# Enclosure_100x68_BHWL.net
KiCad netlist of a schematic drawn in EAGLE
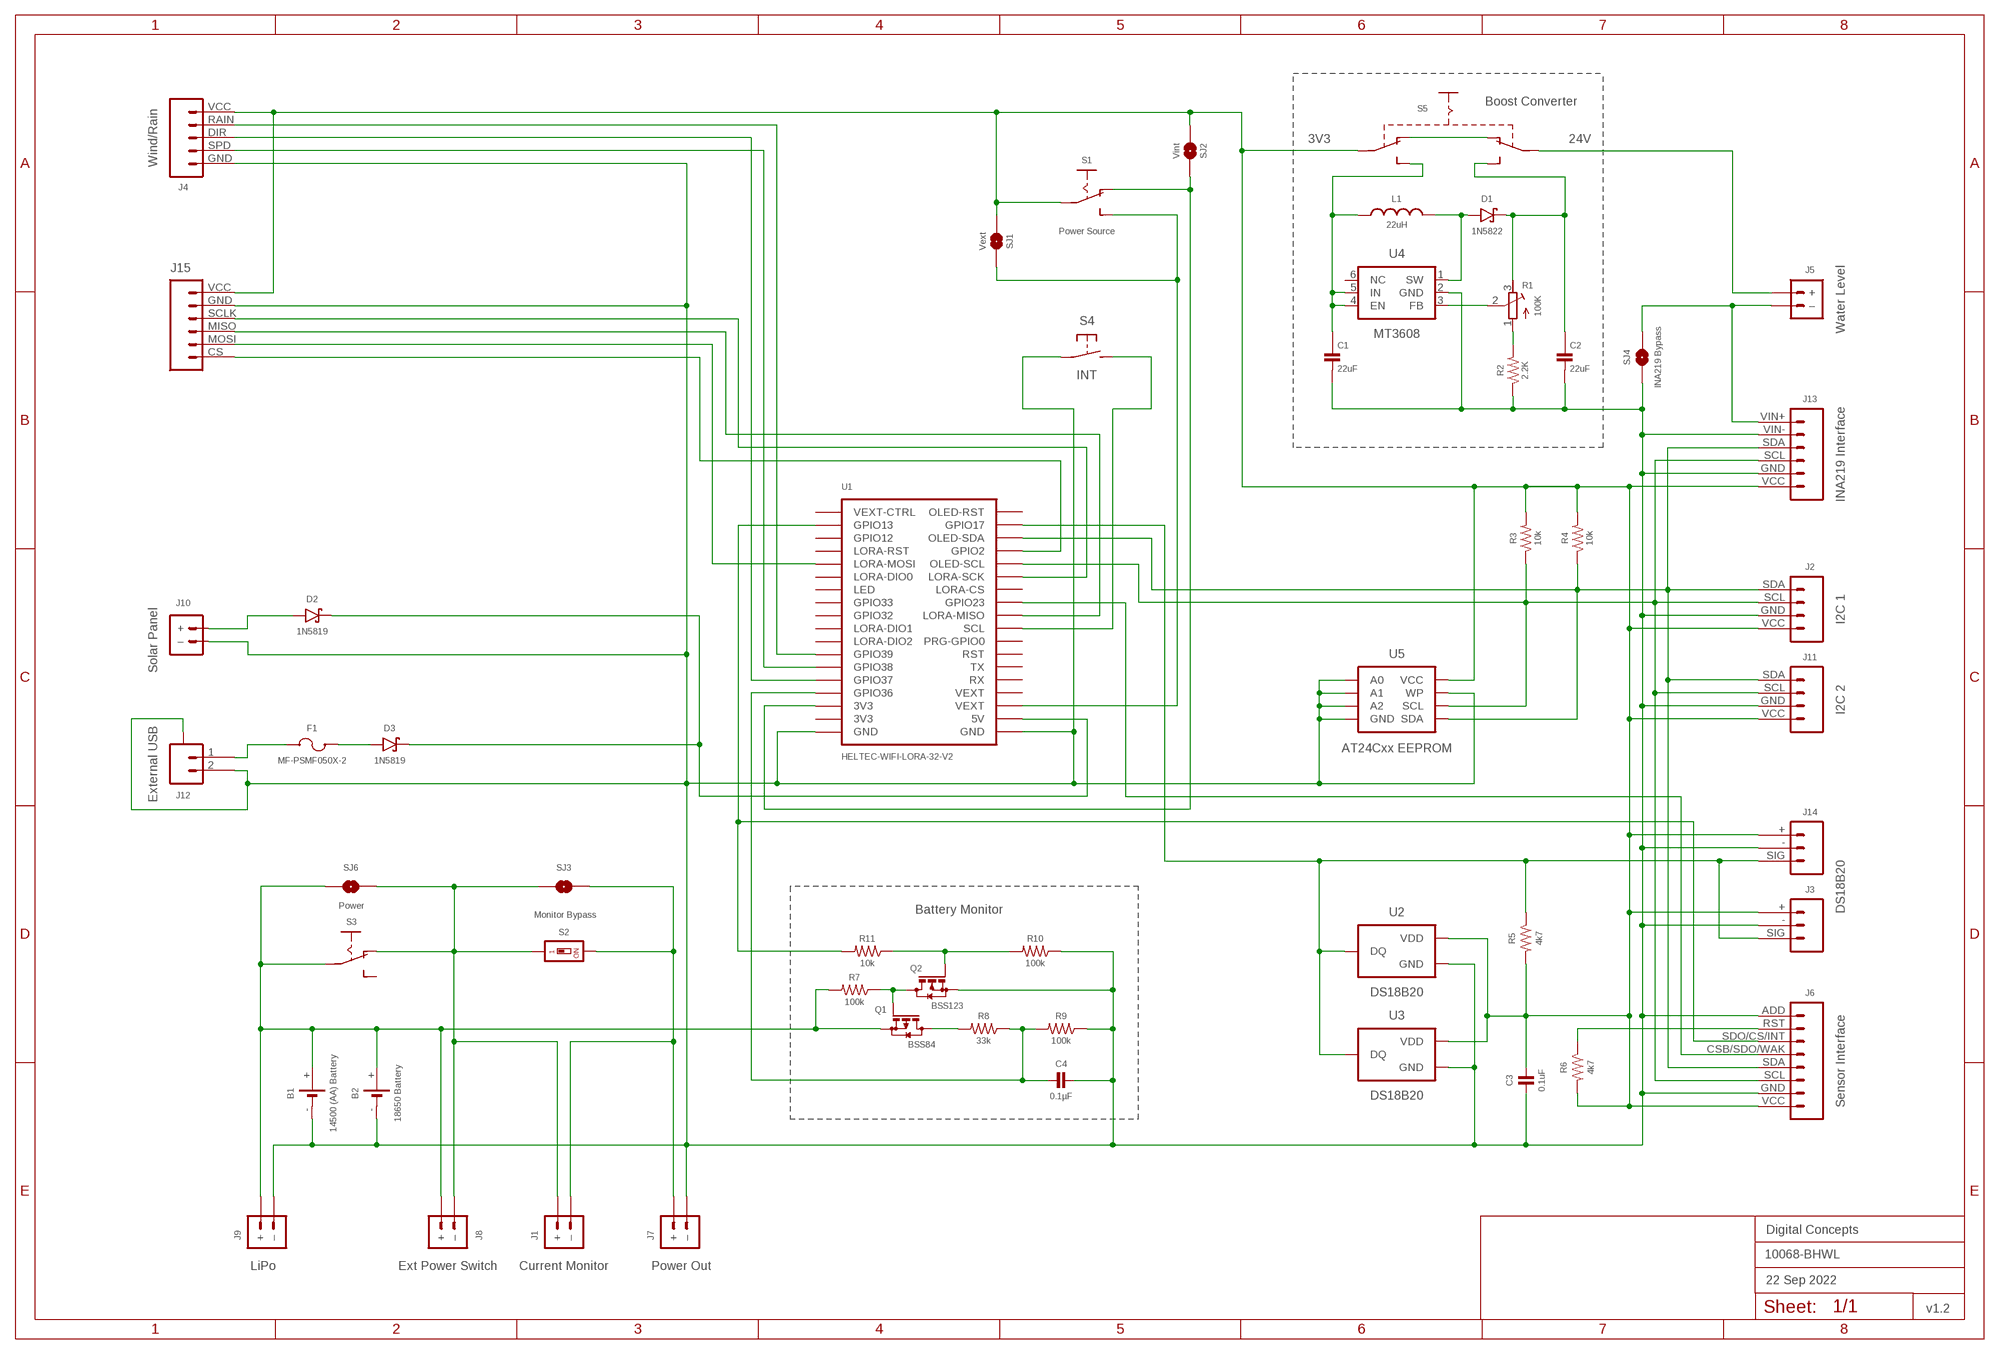
[diagram p0: schematic, sheet 1]

(export (version "E")
  (design (tool "Eeschema 10.0.6"))
  (components
    (comp (ref "B1")
      (value "14500 (AA) Battery")
      (footprint "eagle-import:BATTERY-14500")
      (libsource (lib "eagle-import") (part "BATTERY-HOLDER-14500(AA)"))
    )
    (comp (ref "B2")
      (value "18650 Battery")
      (footprint "eagle-import:BATTERY-18650")
      (libsource (lib "eagle-import") (part "BATTERY-HOLDER-18650"))
    )
    (comp (ref "C1")
      (value "22uF")
      (footprint "eagle-import:C1206")
      (libsource (lib "eagle-import") (part "CAPACITOR-1206"))
    )
    (comp (ref "C2")
      (value "22uF")
      (footprint "eagle-import:C1206")
      (libsource (lib "eagle-import") (part "CAPACITOR-1206"))
    )
    (comp (ref "C3")
      (value "0.1uF")
      (footprint "eagle-import:C0805")
      (libsource (lib "eagle-import") (part "CAPACITOR-0805"))
    )
    (comp (ref "C4")
      (value "0.1µF")
      (footprint "eagle-import:C0805")
      (libsource (lib "eagle-import") (part "CAPACITOR-0805"))
    )
    (comp (ref "D1")
      (value "1N5822")
      (footprint "eagle-import:DIODE_SMB")
      (libsource (lib "eagle-import") (part "DIODE-SCHOTTKY-1N5822"))
    )
    (comp (ref "D2")
      (value "1N5819")
      (footprint "eagle-import:SOD-123")
      (libsource (lib "eagle-import") (part "1N5819-SOD-123"))
    )
    (comp (ref "D3")
      (value "1N5819")
      (footprint "eagle-import:SOD-123")
      (libsource (lib "eagle-import") (part "1N5819-SOD-123"))
    )
    (comp (ref "F1")
      (value "MF-PSMF050X-2")
      (footprint "eagle-import:F0805")
      (libsource (lib "eagle-import") (part "MF-PSMF050X-2"))
    )
    (comp (ref "J1")
      (value "Current Monitor")
      (footprint "eagle-import:JST-PH2.0-2-HORIZONTAL")
      (libsource (lib "eagle-import") (part "JST-PH2.0-2-HORIZONTALJST-PTH-2"))
    )
    (comp (ref "J2")
      (value "I2C 1")
      (footprint "eagle-import:JST-PH2.0-4-VERTICAL-I2C")
      (libsource (lib "eagle-import") (part "JST-PH2.0-4-VERTICAL-I2C"))
    )
    (comp (ref "J3")
      (value "DS18B20")
      (footprint "eagle-import:JST-PH2.0-3-VERTICAL-SIG")
      (libsource (lib "eagle-import") (part "JST-PH2.0-3-VERTICAL-DS18B20"))
    )
    (comp (ref "J4")
      (value "Wind/Rain")
      (footprint "eagle-import:JST-PH2.0-5-DUAL-WEATHER")
      (libsource (lib "eagle-import") (part "JST-PH2.0-5-DUAL-WEATHER"))
    )
    (comp (ref "J5")
      (value "Water Level")
      (footprint "eagle-import:JST-PH2.0-2-DUAL-POWER")
      (libsource (lib "eagle-import") (part "JST-PH2.0-2-DUAL-POWERJST-PTH-2"))
    )
    (comp (ref "J6")
      (value "Sensor Interface")
      (footprint "eagle-import:CONN_08-SENSOR")
      (libsource (lib "eagle-import") (part "HEADER-1X8-SENSOR"))
    )
    (comp (ref "J7")
      (value "Power Out")
      (footprint "eagle-import:JST-GH1.25-2-HORIZONTAL")
      (libsource (lib "eagle-import") (part "JST-GH1.25-2-HORIZONTAL-POWER"))
    )
    (comp (ref "J8")
      (value "Ext Power Switch")
      (footprint "eagle-import:JST-PH2.0-2-DUAL-POWER")
      (libsource (lib "eagle-import") (part "JST-PH2.0-2-DUAL-POWERJST-PTH-2"))
    )
    (comp (ref "J9")
      (value "LiPo")
      (footprint "eagle-import:JST-PH2.0-2-HORIZONTAL-POWER")
      (libsource (lib "eagle-import") (part "JST-PH2.0-2-HORIZONTAL-POWERJST-PTH-2"))
    )
    (comp (ref "J10")
      (value "Solar Panel")
      (footprint "eagle-import:JST-PH2.0-2-VERTICAL=POWER")
      (libsource (lib "eagle-import") (part "JST-PH2.0-2-VERTICAL"))
    )
    (comp (ref "J11")
      (value "I2C 2")
      (footprint "eagle-import:JST-PH2.0-4-HORIZONTAL")
      (libsource (lib "eagle-import") (part "JST-PH2.0-I2C-MALE-HORIZONTAL"))
    )
    (comp (ref "J12")
      (value "External USB")
      (footprint "eagle-import:JST-SH1.0-2-HORIZONTAL")
      (libsource (lib "eagle-import") (part "JST-SH1.0-2-SMD-HORIZONTAL"))
    )
    (comp (ref "J13")
      (value "INA219 Interface")
      (footprint "eagle-import:CONN_06-INA219")
      (libsource (lib "eagle-import") (part "INA219-I2C-MODULE"))
    )
    (comp (ref "J14")
      (value "JST-PH2.0-3-HORIZONTAL-DS18B20")
      (footprint "eagle-import:JST-PH2.0-DS18B20-HORIZONTAL")
      (libsource (lib "eagle-import") (part "JST-PH2.0-3-HORIZONTAL-DS18B20"))
    )
    (comp (ref "J15")
      (value "JST-PH2.0-6-HORIZONTAL-SPI")
      (footprint "eagle-import:JST-PH2.0-6-HORIZONTAL-SPI")
      (libsource (lib "eagle-import") (part "JST-PH2.0-6-HORIZONTAL-SPI"))
    )
    (comp (ref "L1")
      (value "22uH")
      (footprint "eagle-import:CDRH104R+6D28")
      (libsource (lib "eagle-import") (part "INDUCTOR-CDRH104R/6D28L5038P"))
    )
    (comp (ref "Q1")
      (value "BSS84")
      (footprint "eagle-import:SOT23-3")
      (libsource (lib "eagle-import") (part "BSS84"))
    )
    (comp (ref "Q2")
      (value "BSS123")
      (footprint "eagle-import:SOT23-3")
      (libsource (lib "eagle-import") (part "MOSFET-BSS123"))
    )
    (comp (ref "R1")
      (value "100K")
      (footprint "eagle-import:RTRIM64P")
      (libsource (lib "eagle-import") (part "RESISTOR-TRIMM-BAOTER-HORIZONTAL"))
    )
    (comp (ref "R2")
      (value "2.2K")
      (footprint "eagle-import:R0805")
      (libsource (lib "eagle-import") (part "RESISTORR0805"))
    )
    (comp (ref "R3")
      (value "10k")
      (footprint "eagle-import:R0805")
      (libsource (lib "eagle-import") (part "RESISTORR0805"))
    )
    (comp (ref "R4")
      (value "10k")
      (footprint "eagle-import:R0805")
      (libsource (lib "eagle-import") (part "RESISTORR0805"))
    )
    (comp (ref "R5")
      (value "4k7")
      (footprint "eagle-import:R0805")
      (libsource (lib "eagle-import") (part "RESISTORR0805"))
    )
    (comp (ref "R6")
      (value "4k7")
      (footprint "eagle-import:R0805")
      (libsource (lib "eagle-import") (part "RESISTORR0805"))
    )
    (comp (ref "R7")
      (value "100k")
      (footprint "eagle-import:R0805")
      (libsource (lib "eagle-import") (part "RESISTORR0805"))
    )
    (comp (ref "R8")
      (value "33k")
      (footprint "eagle-import:R0805")
      (libsource (lib "eagle-import") (part "RESISTORR0805"))
    )
    (comp (ref "R9")
      (value "100k")
      (footprint "eagle-import:R0805")
      (libsource (lib "eagle-import") (part "RESISTORR0805"))
    )
    (comp (ref "R10")
      (value "100k")
      (footprint "eagle-import:R0805")
      (libsource (lib "eagle-import") (part "RESISTORR0805"))
    )
    (comp (ref "R11")
      (value "10k")
      (footprint "eagle-import:R0805")
      (libsource (lib "eagle-import") (part "RESISTORR0805"))
    )
    (comp (ref "S1")
      (value "Power Source")
      (footprint "eagle-import:SWITCH-SPDT-SMT")
      (libsource (lib "eagle-import") (part "SWITCH-SLIDE-SPDT-SMT"))
    )
    (comp (ref "S2")
      (value "Monitor Bypass")
      (footprint "eagle-import:SMD-001")
      (libsource (lib "eagle-import") (part "SWITCH-DIP-SWS001"))
    )
    (comp (ref "S3")
      (value "Power")
      (footprint "eagle-import:SWITCH-SPDT-PTH")
      (libsource (lib "eagle-import") (part "SWITCH-SLIDE-SPDT-PTH"))
    )
    (comp (ref "S4")
      (value "INT")
      (footprint "eagle-import:SWITCH-2-PAD")
      (libsource (lib "eagle-import") (part "SWITCH-MOMENTARY-2-PIN"))
    )
    (comp (ref "S5")
      (value "SWITCH-SLIDE-DPDT-PTH-S")
      (footprint "eagle-import:SWITCH-DPDT-PTH")
      (libsource (lib "eagle-import") (part "SWITCH-SLIDE-DPDT-PTH-S"))
    )
    (comp (ref "SJ1")
      (value "Vext")
      (footprint "eagle-import:SJ")
      (libsource (lib "eagle-import") (part "SJ"))
    )
    (comp (ref "SJ2")
      (value "Vint")
      (footprint "eagle-import:SJ-VIA-2")
      (libsource (lib "eagle-import") (part "SJ-V-2"))
    )
    (comp (ref "SJ3")
      (value "Monitor")
      (footprint "eagle-import:SJ")
      (libsource (lib "eagle-import") (part "SJ"))
    )
    (comp (ref "SJ4")
      (value "INA219 Bypass")
      (footprint "eagle-import:SJ")
      (libsource (lib "eagle-import") (part "SJ"))
    )
    (comp (ref "SJ6")
      (value "Power")
      (footprint "eagle-import:SJ")
      (libsource (lib "eagle-import") (part "SJ"))
    )
    (comp (ref "U1")
      (value "HELTEC-WIFI-LORA-32-V2")
      (footprint "eagle-import:HELTEC-WIFI-LORA-32-V2")
      (libsource (lib "eagle-import") (part "HELTEC-WIFI-LORA-32-V2"))
    )
    (comp (ref "U2")
      (value "DS18B20")
      (footprint "eagle-import:TO-92")
      (fields (field (name "MF") "Maxim Integrated"))
      (libsource (lib "eagle-import") (part "THERMOMETER-DS18B20"))
    )
    (comp (ref "U3")
      (value "DS18B20")
      (footprint "eagle-import:TO-92")
      (fields (field (name "MF") "Maxim Integrated"))
      (libsource (lib "eagle-import") (part "THERMOMETER-DS18B20"))
    )
    (comp (ref "U4")
      (value "MT3608")
      (footprint "eagle-import:SOT-23-6")
      (libsource (lib "eagle-import") (part "MT3608"))
    )
    (comp (ref "U5")
      (value "AT24Cxx EEPROM")
      (footprint "eagle-import:SOP-8")
      (libsource (lib "eagle-import") (part "AT24CXX-EEPROM"))
    )
  )
  (nets
    (net (code "1") (name "Net-(C4-Pad1)") (class "Default")
      (node (ref "C4") (pin "1") (pinfunction "1_1") (pintype "passive"))
      (node (ref "R8") (pin "1") (pinfunction "1_1") (pintype "passive"))
      (node (ref "R9") (pin "2") (pinfunction "2_2") (pintype "passive"))
      (node (ref "U1") (pin "GPIO36") (pinfunction "GPIO36_GPIO36") (pintype "bidirectional"))
    )
    (net (code "2") (name "Net-(D2-PadA)") (class "Default")
      (node (ref "D2") (pin "A") (pinfunction "A_A") (pintype "passive"))
      (node (ref "J10") (pin "+") (pinfunction "+_+") (pintype "power_in"))
    )
    (net (code "3") (name "Net-(D2-PadC)") (class "Default")
      (node (ref "D2") (pin "C") (pinfunction "C_C") (pintype "passive"))
      (node (ref "D3") (pin "C") (pinfunction "C_C") (pintype "passive"))
      (node (ref "U1") (pin "5V") (pinfunction "5V_5V") (pintype "bidirectional"))
    )
    (net (code "4") (name "Net-(D3-PadA)") (class "Default")
      (node (ref "D3") (pin "A") (pinfunction "A_A") (pintype "passive"))
      (node (ref "F1") (pin "1") (pinfunction "1_1") (pintype "passive"))
    )
    (net (code "5") (name "Net-(F1-Pad2)") (class "Default")
      (node (ref "F1") (pin "2") (pinfunction "2_2") (pintype "passive"))
      (node (ref "J12") (pin "1") (pinfunction "1_1") (pintype "passive"))
    )
    (net (code "6") (name "Net-(J1-+)") (class "Default")
      (node (ref "J1") (pin "1") (pinfunction "+_1") (pintype "power_in"))
      (node (ref "J8") (pin "-") (pinfunction "–_-") (pintype "power_in"))
      (node (ref "S2") (pin "1") (pinfunction "1_1") (pintype "passive"))
      (node (ref "S3") (pin "1") (pinfunction "O_1") (pintype "passive"))
      (node (ref "SJ3") (pin "2") (pinfunction "2_2") (pintype "passive"))
      (node (ref "SJ6") (pin "1") (pinfunction "1_1") (pintype "passive"))
    )
    (net (code "7") (name "Net-(J1-–)") (class "Default")
      (node (ref "J1") (pin "2") (pinfunction "–_2") (pintype "power_in"))
      (node (ref "J7") (pin "+") (pinfunction "+_+") (pintype "power_in"))
      (node (ref "S2") (pin "2") (pinfunction "2_2") (pintype "passive"))
      (node (ref "SJ3") (pin "1") (pinfunction "1_1") (pintype "passive"))
    )
    (net (code "8") (name "Net-(J4-2)") (class "Default")
      (node (ref "J4") (pin "RAIN") (pinfunction "2_RAIN") (pintype "passive"))
      (node (ref "U1") (pin "GPIO39") (pinfunction "GPIO39_GPIO39") (pintype "bidirectional"))
    )
    (net (code "9") (name "Net-(J4-3)") (class "Default")
      (node (ref "J4") (pin "DIR") (pinfunction "3_DIR") (pintype "passive"))
      (node (ref "U1") (pin "GPIO37") (pinfunction "GPIO37_GPIO37") (pintype "bidirectional"))
    )
    (net (code "10") (name "Net-(J4-4)") (class "Default")
      (node (ref "J4") (pin "SPD") (pinfunction "4_SPD") (pintype "passive"))
      (node (ref "U1") (pin "GPIO38") (pinfunction "GPIO38_GPIO38") (pintype "bidirectional"))
    )
    (net (code "11") (name "Net-(J6-5)") (class "Default")
      (node (ref "J6") (pin "CSB/SDO/WAK") (pinfunction "5_CSB/SDO/WAK") (pintype "passive"))
      (node (ref "U1") (pin "GPIO23") (pinfunction "GPIO23_GPIO23") (pintype "bidirectional"))
    )
    (net (code "12") (name "Net-(J6-6)") (class "Default")
      (node (ref "J6") (pin "SDO/CS/INT") (pinfunction "6_SDO/CS/INT") (pintype "passive"))
      (node (ref "R11") (pin "2") (pinfunction "2_2") (pintype "passive"))
      (node (ref "U1") (pin "GPIO13") (pinfunction "GPIO13_GPIO13") (pintype "bidirectional"))
    )
    (net (code "13") (name "Net-(J6-7)") (class "Default")
      (node (ref "J6") (pin "RST") (pinfunction "7_RST") (pintype "passive"))
      (node (ref "R6") (pin "1") (pinfunction "1_1") (pintype "passive"))
    )
    (net (code "14") (name "Net-(J10-–)") (class "Default")
      (node (ref "B1") (pin "-") (pinfunction "-_-") (pintype "power_in"))
      (node (ref "B2") (pin "-") (pinfunction "-_-") (pintype "power_in"))
      (node (ref "C1") (pin "2") (pinfunction "2_2") (pintype "passive"))
      (node (ref "C2") (pin "2") (pinfunction "2_2") (pintype "passive"))
      (node (ref "C3") (pin "2") (pinfunction "2_2") (pintype "passive"))
      (node (ref "C4") (pin "2") (pinfunction "2_2") (pintype "passive"))
      (node (ref "J10") (pin "-") (pinfunction "–_-") (pintype "power_in"))
      (node (ref "J11") (pin "GND") (pinfunction "2_GND") (pintype "passive"))
      (node (ref "J12") (pin "2") (pinfunction "2_2") (pintype "passive"))
      (node (ref "J12") (pin "A@1") (pinfunction "A_A@1") (pintype "power_in"))
      (node (ref "J12") (pin "A@2") (pinfunction "A_A@2") (pintype "power_in"))
      (node (ref "J13") (pin "GND") (pinfunction "2_GND") (pintype "passive"))
      (node (ref "J13") (pin "VIN-") (pinfunction "5_VIN-") (pintype "passive"))
      (node (ref "J14") (pin "-") (pinfunction "2_-") (pintype "passive"))
      (node (ref "J15") (pin "GND") (pinfunction "5_GND") (pintype "passive"))
      (node (ref "J2") (pin "GND") (pinfunction "3_GND") (pintype "passive"))
      (node (ref "J3") (pin "-") (pinfunction "2_-") (pintype "passive"))
      (node (ref "J4") (pin "GND") (pinfunction "5_GND") (pintype "passive"))
      (node (ref "J6") (pin "ADD") (pinfunction "8_ADD") (pintype "passive"))
      (node (ref "J6") (pin "GND") (pinfunction "2_GND") (pintype "passive"))
      (node (ref "J7") (pin "-") (pinfunction "–_-") (pintype "power_in"))
      (node (ref "J9") (pin "-") (pinfunction "–_-") (pintype "power_in"))
      (node (ref "Q2") (pin "2") (pinfunction "S_2") (pintype "passive"))
      (node (ref "R10") (pin "1") (pinfunction "1_1") (pintype "passive"))
      (node (ref "R2") (pin "1") (pinfunction "1_1") (pintype "passive"))
      (node (ref "R9") (pin "1") (pinfunction "1_1") (pintype "passive"))
      (node (ref "S4") (pin "P$1") (pinfunction "P_P$1") (pintype "passive"))
      (node (ref "SJ4") (pin "1") (pinfunction "1_1") (pintype "passive"))
      (node (ref "U1") (pin "GND@1") (pinfunction "GND_GND@1") (pintype "bidirectional"))
      (node (ref "U1") (pin "GND@36") (pinfunction "GND_GND@36") (pintype "bidirectional"))
      (node (ref "U2") (pin "1") (pinfunction "GND_1") (pintype "power_in"))
      (node (ref "U3") (pin "1") (pinfunction "GND_1") (pintype "power_in"))
      (node (ref "U4") (pin "2") (pinfunction "GND_2") (pintype "power_in"))
      (node (ref "U5") (pin "P$1") (pinfunction "A0_P$1") (pintype "bidirectional"))
      (node (ref "U5") (pin "P$2") (pinfunction "A1_P$2") (pintype "bidirectional"))
      (node (ref "U5") (pin "P$3") (pinfunction "A2_P$3") (pintype "bidirectional"))
      (node (ref "U5") (pin "P$4") (pinfunction "GND_P$4") (pintype "bidirectional"))
      (node (ref "U5") (pin "P$7") (pinfunction "WP_P$7") (pintype "bidirectional"))
    )
    (net (code "15") (name "Net-(J11-1)") (class "Default")
      (node (ref "C3") (pin "1") (pinfunction "1_1") (pintype "passive"))
      (node (ref "J11") (pin "VCC") (pinfunction "1_VCC") (pintype "passive"))
      (node (ref "J13") (pin "VCC") (pinfunction "1_VCC") (pintype "passive"))
      (node (ref "J14") (pin "+") (pinfunction "3_+") (pintype "passive"))
      (node (ref "J15") (pin "VCC") (pinfunction "6_VCC") (pintype "passive"))
      (node (ref "J2") (pin "VCC") (pinfunction "4_VCC") (pintype "passive"))
      (node (ref "J3") (pin "+") (pinfunction "3_+") (pintype "passive"))
      (node (ref "J4") (pin "VCC") (pinfunction "1_VCC") (pintype "passive"))
      (node (ref "J6") (pin "VCC") (pinfunction "1_VCC") (pintype "passive"))
      (node (ref "R3") (pin "2") (pinfunction "2_2") (pintype "passive"))
      (node (ref "R4") (pin "2") (pinfunction "2_2") (pintype "passive"))
      (node (ref "R5") (pin "2") (pinfunction "2_2") (pintype "passive"))
      (node (ref "R6") (pin "2") (pinfunction "2_2") (pintype "passive"))
      (node (ref "S1") (pin "2") (pinfunction "P_2") (pintype "passive"))
      (node (ref "S5") (pin "P$5") (pinfunction "P2_P$5") (pintype "passive"))
      (node (ref "SJ1") (pin "2") (pinfunction "2_2") (pintype "passive"))
      (node (ref "SJ2") (pin "2") (pinfunction "2_2") (pintype "passive"))
      (node (ref "SJ2") (pin "2@V") (pinfunction "2_2@V") (pintype "passive"))
      (node (ref "U2") (pin "3") (pinfunction "VDD_3") (pintype "power_in"))
      (node (ref "U3") (pin "3") (pinfunction "VDD_3") (pintype "power_in"))
      (node (ref "U5") (pin "P$8") (pinfunction "VCC_P$8") (pintype "bidirectional"))
    )
    (net (code "16") (name "Net-(J11-3)") (class "Default")
      (node (ref "J11") (pin "SCL") (pinfunction "3_SCL") (pintype "passive"))
      (node (ref "J13") (pin "SCL") (pinfunction "3_SCL") (pintype "passive"))
      (node (ref "J2") (pin "SCL") (pinfunction "2_SCL") (pintype "passive"))
      (node (ref "J6") (pin "SCL") (pinfunction "3_SCL") (pintype "passive"))
      (node (ref "R3") (pin "1") (pinfunction "1_1") (pintype "passive"))
      (node (ref "U1") (pin "GPIO15") (pinfunction "OLED-SCL_GPIO15") (pintype "bidirectional"))
      (node (ref "U5") (pin "P$6") (pinfunction "SCL_P$6") (pintype "bidirectional"))
    )
    (net (code "17") (name "Net-(J11-4)") (class "Default")
      (node (ref "J11") (pin "SDA") (pinfunction "4_SDA") (pintype "passive"))
      (node (ref "J13") (pin "SDA") (pinfunction "4_SDA") (pintype "passive"))
      (node (ref "J2") (pin "SDA") (pinfunction "1_SDA") (pintype "passive"))
      (node (ref "J6") (pin "SDA") (pinfunction "4_SDA") (pintype "passive"))
      (node (ref "R4") (pin "1") (pinfunction "1_1") (pintype "passive"))
      (node (ref "U1") (pin "GPIO4") (pinfunction "OLED-SDA_GPIO4") (pintype "bidirectional"))
      (node (ref "U5") (pin "P$5") (pinfunction "SDA_P$5") (pintype "bidirectional"))
    )
    (net (code "18") (name "Net-(J13-6)") (class "Default")
      (node (ref "J13") (pin "VIN+") (pinfunction "6_VIN+") (pintype "passive"))
      (node (ref "J5") (pin "-") (pinfunction "–_-") (pintype "power_in"))
      (node (ref "SJ4") (pin "2") (pinfunction "2_2") (pintype "passive"))
    )
    (net (code "19") (name "Net-(J14-1)") (class "Default")
      (node (ref "J14") (pin "SIG") (pinfunction "1_SIG") (pintype "passive"))
      (node (ref "J3") (pin "SIG") (pinfunction "1_SIG") (pintype "passive"))
      (node (ref "R5") (pin "1") (pinfunction "1_1") (pintype "passive"))
      (node (ref "U1") (pin "GPIO17") (pinfunction "GPIO17_GPIO17") (pintype "bidirectional"))
      (node (ref "U2") (pin "2") (pinfunction "DQ_2") (pintype "bidirectional"))
      (node (ref "U3") (pin "2") (pinfunction "DQ_2") (pintype "bidirectional"))
    )
    (net (code "20") (name "Net-(J15-1)") (class "Default")
      (node (ref "J15") (pin "CS") (pinfunction "1_CS") (pintype "passive"))
      (node (ref "U1") (pin "GPIO2") (pinfunction "GPIO2_GPIO2") (pintype "bidirectional"))
    )
    (net (code "21") (name "Net-(J15-2)") (class "Default")
      (node (ref "J15") (pin "MOSI") (pinfunction "2_MOSI") (pintype "passive"))
      (node (ref "U1") (pin "GPIO27") (pinfunction "LORA-MOSI_GPIO27") (pintype "bidirectional"))
    )
    (net (code "22") (name "Net-(J15-3)") (class "Default")
      (node (ref "J15") (pin "MISO") (pinfunction "3_MISO") (pintype "passive"))
      (node (ref "U1") (pin "GPIO19") (pinfunction "LORA-MISO_GPIO19") (pintype "bidirectional"))
    )
    (net (code "23") (name "Net-(J15-4)") (class "Default")
      (node (ref "J15") (pin "SCLK") (pinfunction "4_SCLK") (pintype "passive"))
      (node (ref "U1") (pin "GPIO5") (pinfunction "LORA-SCK_GPIO5") (pintype "bidirectional"))
    )
    (net (code "24") (name "Net-(Q1-D)") (class "Default")
      (node (ref "Q1") (pin "3") (pinfunction "D_3") (pintype "passive"))
      (node (ref "R8") (pin "2") (pinfunction "2_2") (pintype "passive"))
    )
    (net (code "25") (name "Net-(Q1-G)") (class "Default")
      (node (ref "Q1") (pin "1") (pinfunction "G_1") (pintype "passive"))
      (node (ref "Q2") (pin "3") (pinfunction "D_3") (pintype "passive"))
      (node (ref "R7") (pin "1") (pinfunction "1_1") (pintype "passive"))
    )
    (net (code "26") (name "Net-(Q1-S)") (class "Default")
      (node (ref "B1") (pin "+") (pinfunction "+_+") (pintype "power_in"))
      (node (ref "B2") (pin "+") (pinfunction "+_+") (pintype "power_in"))
      (node (ref "J8") (pin "+") (pinfunction "+_+") (pintype "power_in"))
      (node (ref "J9") (pin "+") (pinfunction "+_+") (pintype "power_in"))
      (node (ref "Q1") (pin "2") (pinfunction "S_2") (pintype "passive"))
      (node (ref "R7") (pin "2") (pinfunction "2_2") (pintype "passive"))
      (node (ref "S3") (pin "2") (pinfunction "P_2") (pintype "passive"))
      (node (ref "SJ6") (pin "2") (pinfunction "2_2") (pintype "passive"))
    )
    (net (code "27") (name "Net-(Q2-G)") (class "Default")
      (node (ref "Q2") (pin "1") (pinfunction "G_1") (pintype "passive"))
      (node (ref "R10") (pin "2") (pinfunction "2_2") (pintype "passive"))
      (node (ref "R11") (pin "1") (pinfunction "1_1") (pintype "passive"))
    )
    (net (code "28") (name "Net-(R1-A)") (class "Default")
      (node (ref "R1") (pin "1") (pinfunction "A_1") (pintype "passive"))
      (node (ref "R2") (pin "2") (pinfunction "2_2") (pintype "passive"))
    )
    (net (code "29") (name "Net-(R1-E)") (class "Default")
      (node (ref "C2") (pin "1") (pinfunction "1_1") (pintype "passive"))
      (node (ref "D1") (pin "C") (pinfunction "C_C") (pintype "passive"))
      (node (ref "R1") (pin "3") (pinfunction "E_3") (pintype "passive"))
      (node (ref "S5") (pin "P$3") (pinfunction "S1_P$3") (pintype "passive"))
    )
    (net (code "30") (name "Net-(R1-S)") (class "Default")
      (node (ref "R1") (pin "2") (pinfunction "S_2") (pintype "passive"))
      (node (ref "U4") (pin "3") (pinfunction "FB_3") (pintype "input"))
    )
    (net (code "31") (name "Net-(S1-O)") (class "Default")
      (node (ref "S1") (pin "1") (pinfunction "O_1") (pintype "passive"))
      (node (ref "SJ2") (pin "1") (pinfunction "1_1") (pintype "passive"))
      (node (ref "U1") (pin "3V3@34") (pinfunction "3V3_3V3@34") (pintype "bidirectional"))
    )
    (net (code "32") (name "Net-(S1-S)") (class "Default")
      (node (ref "S1") (pin "3") (pinfunction "S_3") (pintype "passive"))
      (node (ref "SJ1") (pin "1") (pinfunction "1_1") (pintype "passive"))
      (node (ref "U1") (pin "VEXT@3") (pinfunction "VEXT_VEXT@3") (pintype "bidirectional"))
    )
    (net (code "33") (name "Net-(S4-S)") (class "Default")
      (node (ref "S4") (pin "P$2") (pinfunction "S_P$2") (pintype "passive"))
      (node (ref "U1") (pin "GPIO22") (pinfunction "SCL_GPIO22") (pintype "bidirectional"))
    )
    (net (code "34") (name "Net-(S5-O1)") (class "Default")
      (node (ref "S5") (pin "P$1") (pinfunction "O1_P$1") (pintype "passive"))
      (node (ref "S5") (pin "P$4") (pinfunction "O2_P$4") (pintype "passive"))
    )
    (net (code "35") (name "Net-(S5-P1)") (class "Default")
      (node (ref "J5") (pin "+") (pinfunction "+_+") (pintype "power_in"))
      (node (ref "S5") (pin "P$2") (pinfunction "P1_P$2") (pintype "passive"))
    )
    (net (code "36") (name "Net-(S5-S2)") (class "Default")
      (node (ref "C1") (pin "1") (pinfunction "1_1") (pintype "passive"))
      (node (ref "L1") (pin "2") (pinfunction "2_2") (pintype "passive"))
      (node (ref "S5") (pin "P$6") (pinfunction "S2_P$6") (pintype "passive"))
      (node (ref "U4") (pin "4") (pinfunction "EN_4") (pintype "input"))
      (node (ref "U4") (pin "5") (pinfunction "IN_5") (pintype "power_in"))
    )
    (net (code "37") (name "Net-(U4-SW)") (class "Default")
      (node (ref "D1") (pin "A") (pinfunction "A_A") (pintype "passive"))
      (node (ref "L1") (pin "1") (pinfunction "1_1") (pintype "passive"))
      (node (ref "U4") (pin "1") (pinfunction "SW_1") (pintype "power_in"))
    )
    (net (code "38") (name "unconnected-(S3-S-Pad3)") (class "Default")
      (node (ref "S3") (pin "3") (pinfunction "S_3") (pintype "passive"))
    )
    (net (code "39") (name "unconnected-(U1-3V3-Pad3V3@35)") (class "Default")
      (node (ref "U1") (pin "3V3@35") (pinfunction "3V3_3V3@35") (pintype "bidirectional"))
    )
    (net (code "40") (name "unconnected-(U1-LED-PadGPIO25)") (class "Default")
      (node (ref "U1") (pin "GPIO25") (pinfunction "LED_GPIO25") (pintype "bidirectional"))
    )
    (net (code "41") (name "unconnected-(U1-LORA-CS-PadGPIO18)") (class "Default")
      (node (ref "U1") (pin "GPIO18") (pinfunction "LORA-CS_GPIO18") (pintype "bidirectional"))
    )
    (net (code "42") (name "unconnected-(U1-LORA-DIO0-PadGPIO26)") (class "Default")
      (node (ref "U1") (pin "GPIO26") (pinfunction "LORA-DIO0_GPIO26") (pintype "bidirectional"))
    )
    (net (code "43") (name "unconnected-(U1-LORA-DIO1-PadGPIO35)") (class "Default")
      (node (ref "U1") (pin "GPIO35") (pinfunction "LORA-DIO1_GPIO35") (pintype "bidirectional"))
    )
    (net (code "44") (name "unconnected-(U1-LORA-DIO2-PadGPIO34)") (class "Default")
      (node (ref "U1") (pin "GPIO34") (pinfunction "LORA-DIO2_GPIO34") (pintype "bidirectional"))
    )
    (net (code "45") (name "unconnected-(U1-LORA-RST-PadGPIO14)") (class "Default")
      (node (ref "U1") (pin "GPIO14") (pinfunction "LORA-RST_GPIO14") (pintype "bidirectional"))
    )
    (net (code "46") (name "unconnected-(U1-OLED-RST-PadGPIO16)") (class "Default")
      (node (ref "U1") (pin "GPIO16") (pinfunction "OLED-RST_GPIO16") (pintype "bidirectional"))
    )
    (net (code "47") (name "unconnected-(U1-PRG-GPIO0-PadGPIO0)") (class "Default")
      (node (ref "U1") (pin "GPIO0") (pinfunction "PRG-GPIO0_GPIO0") (pintype "bidirectional"))
    )
    (net (code "48") (name "unconnected-(U1-PadGPIO12)") (class "Default")
      (node (ref "U1") (pin "GPIO12") (pinfunction "GPIO12_GPIO12") (pintype "bidirectional"))
    )
    (net (code "49") (name "unconnected-(U1-PadGPIO32)") (class "Default")
      (node (ref "U1") (pin "GPIO32") (pinfunction "GPIO32_GPIO32") (pintype "bidirectional"))
    )
    (net (code "50") (name "unconnected-(U1-PadGPIO33)") (class "Default")
      (node (ref "U1") (pin "GPIO33") (pinfunction "GPIO33_GPIO33") (pintype "bidirectional"))
    )
    (net (code "51") (name "unconnected-(U1-PadRST)") (class "Default")
      (node (ref "U1") (pin "RST") (pinfunction "RST_RST") (pintype "bidirectional"))
    )
    (net (code "52") (name "unconnected-(U1-PadRX)") (class "Default")
      (node (ref "U1") (pin "RX") (pinfunction "RX_RX") (pintype "bidirectional"))
    )
    (net (code "53") (name "unconnected-(U1-PadTX)") (class "Default")
      (node (ref "U1") (pin "TX") (pinfunction "TX_TX") (pintype "bidirectional"))
    )
    (net (code "54") (name "unconnected-(U1-VEXT-CTRL-PadGPIO21)") (class "Default")
      (node (ref "U1") (pin "GPIO21") (pinfunction "VEXT-CTRL_GPIO21") (pintype "bidirectional"))
    )
    (net (code "55") (name "unconnected-(U1-VEXT-PadVEXT@4)") (class "Default")
      (node (ref "U1") (pin "VEXT@4") (pinfunction "VEXT_VEXT@4") (pintype "bidirectional"))
    )
    (net (code "56") (name "unconnected-(U4-NC-Pad6)") (class "Default")
      (node (ref "U4") (pin "6") (pinfunction "NC_6") (pintype "no_connect"))
    )
  )
)
